# IMU.net
KiCad netlist of a schematic drawn in Altium Designer
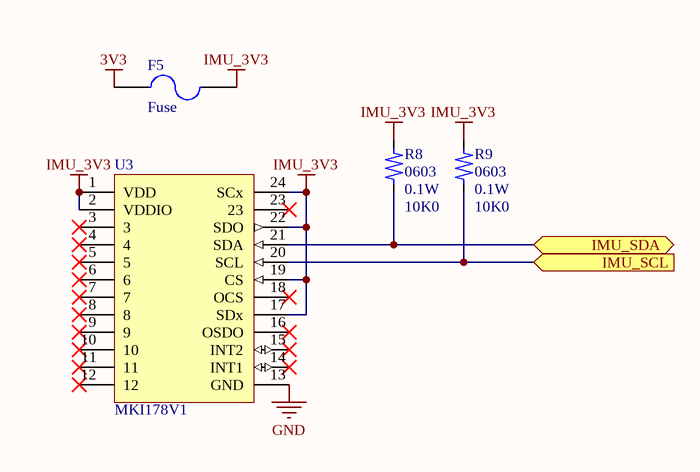
[diagram p0: IMU.SchDoc]

(export (version "E")
  (design (tool "Eeschema 10.0.6"))
  (components
    (comp (ref "F5")
      (value "Fuse")
      (footprint "F_0603")
      (fields (field (name "PART NUMBER") "MC06CF.500") (field (name "NI PART NUMBER") "766324-01"))
      (libsource (lib "Components") (part "Fuse"))
    )
    (comp (ref "R8")
      (value "0603")
      (footprint "R_0603")
      (fields
        (field (name "TOLERANCE") "1%")
        (field (name "PART NUMBER") "CR-03FL7---10K")
        (field (name "RATING") "0.1W")
        (field (name "ALTIUM_VALUE") "10K0")
        (field (name "NI PART NUMBER") "713771-01")
      )
      (libsource (lib "Components") (part "Resistor_Chip"))
    )
    (comp (ref "R9")
      (value "0603")
      (footprint "R_0603")
      (fields
        (field (name "TOLERANCE") "1%")
        (field (name "PART NUMBER") "CR-03FL7---10K")
        (field (name "RATING") "0.1W")
        (field (name "ALTIUM_VALUE") "10K0")
        (field (name "NI PART NUMBER") "713771-01")
      )
      (libsource (lib "Components") (part "Resistor_Chip"))
    )
    (comp (ref "U3")
      (value "MKI178V1")
      (footprint "FP_DIL24")
      (description "LSM6DSL inertial module adapter")
      (libsource (lib "hallglib") (part "MKI178V1"))
    )
  )
  (nets
    (net (code "1") (name "/IMU_SCL") (class "Default")
      (node (ref "R9") (pin "1") (pinfunction "R1_1") (pintype "passive"))
      (node (ref "U3") (pin "20") (pinfunction "SCL_20") (pintype "input"))
    )
    (net (code "2") (name "/IMU_SDA") (class "Default")
      (node (ref "R8") (pin "1") (pinfunction "R1_1") (pintype "passive"))
      (node (ref "U3") (pin "21") (pinfunction "SDA_21") (pintype "input"))
    )
    (net (code "3") (name "3V3") (class "Default")
      (node (ref "F5") (pin "1") (pinfunction "1_1") (pintype "passive"))
    )
    (net (code "4") (name "GND") (class "Default")
      (node (ref "U3") (pin "13") (pinfunction "GND_13") (pintype "power_in"))
    )
    (net (code "5") (name "IMU_3V3") (class "Default")
      (node (ref "F5") (pin "2") (pinfunction "2_2") (pintype "passive"))
      (node (ref "R8") (pin "2") (pinfunction "R2_2") (pintype "passive"))
      (node (ref "R9") (pin "2") (pinfunction "R2_2") (pintype "passive"))
      (node (ref "U3") (pin "1") (pinfunction "VDD_1") (pintype "power_in"))
      (node (ref "U3") (pin "17") (pinfunction "SDx_17") (pintype "passive"))
      (node (ref "U3") (pin "19") (pinfunction "CS_19") (pintype "input"))
      (node (ref "U3") (pin "2") (pinfunction "VDDIO_2") (pintype "power_in"))
      (node (ref "U3") (pin "22") (pinfunction "SDO_22") (pintype "output"))
      (node (ref "U3") (pin "24") (pinfunction "SCx_24") (pintype "passive"))
    )
    (net (code "6") (name "unconnected-(U3-INT1-Pad14)") (class "Default")
      (node (ref "U3") (pin "14") (pinfunction "INT1_14") (pintype "bidirectional+no_connect"))
    )
    (net (code "7") (name "unconnected-(U3-INT2-Pad15)") (class "Default")
      (node (ref "U3") (pin "15") (pinfunction "INT2_15") (pintype "bidirectional+no_connect"))
    )
    (net (code "8") (name "unconnected-(U3-OCS-Pad18)") (class "Default")
      (node (ref "U3") (pin "18") (pinfunction "OCS_18") (pintype "passive+no_connect"))
    )
    (net (code "9") (name "unconnected-(U3-OSDO-Pad16)") (class "Default")
      (node (ref "U3") (pin "16") (pinfunction "OSDO_16") (pintype "passive+no_connect"))
    )
    (net (code "10") (name "unconnected-(U3-Pad3)") (class "Default")
      (node (ref "U3") (pin "3") (pinfunction "3_3") (pintype "passive+no_connect"))
    )
    (net (code "11") (name "unconnected-(U3-Pad4)") (class "Default")
      (node (ref "U3") (pin "4") (pinfunction "4_4") (pintype "passive+no_connect"))
    )
    (net (code "12") (name "unconnected-(U3-Pad5)") (class "Default")
      (node (ref "U3") (pin "5") (pinfunction "5_5") (pintype "passive+no_connect"))
    )
    (net (code "13") (name "unconnected-(U3-Pad6)") (class "Default")
      (node (ref "U3") (pin "6") (pinfunction "6_6") (pintype "passive+no_connect"))
    )
    (net (code "14") (name "unconnected-(U3-Pad7)") (class "Default")
      (node (ref "U3") (pin "7") (pinfunction "7_7") (pintype "passive+no_connect"))
    )
    (net (code "15") (name "unconnected-(U3-Pad8)") (class "Default")
      (node (ref "U3") (pin "8") (pinfunction "8_8") (pintype "passive+no_connect"))
    )
    (net (code "16") (name "unconnected-(U3-Pad9)") (class "Default")
      (node (ref "U3") (pin "9") (pinfunction "9_9") (pintype "passive+no_connect"))
    )
    (net (code "17") (name "unconnected-(U3-Pad10)") (class "Default")
      (node (ref "U3") (pin "10") (pinfunction "10_10") (pintype "passive+no_connect"))
    )
    (net (code "18") (name "unconnected-(U3-Pad11)") (class "Default")
      (node (ref "U3") (pin "11") (pinfunction "11_11") (pintype "passive+no_connect"))
    )
    (net (code "19") (name "unconnected-(U3-Pad12)") (class "Default")
      (node (ref "U3") (pin "12") (pinfunction "12_12") (pintype "passive+no_connect"))
    )
    (net (code "20") (name "unconnected-(U3-Pad23)") (class "Default")
      (node (ref "U3") (pin "23") (pinfunction "23_23") (pintype "passive+no_connect"))
    )
  )
)
